# M5amigo-RS-485-MAX3485ECSA.net
KiCad netlist of a schematic drawn in EAGLE
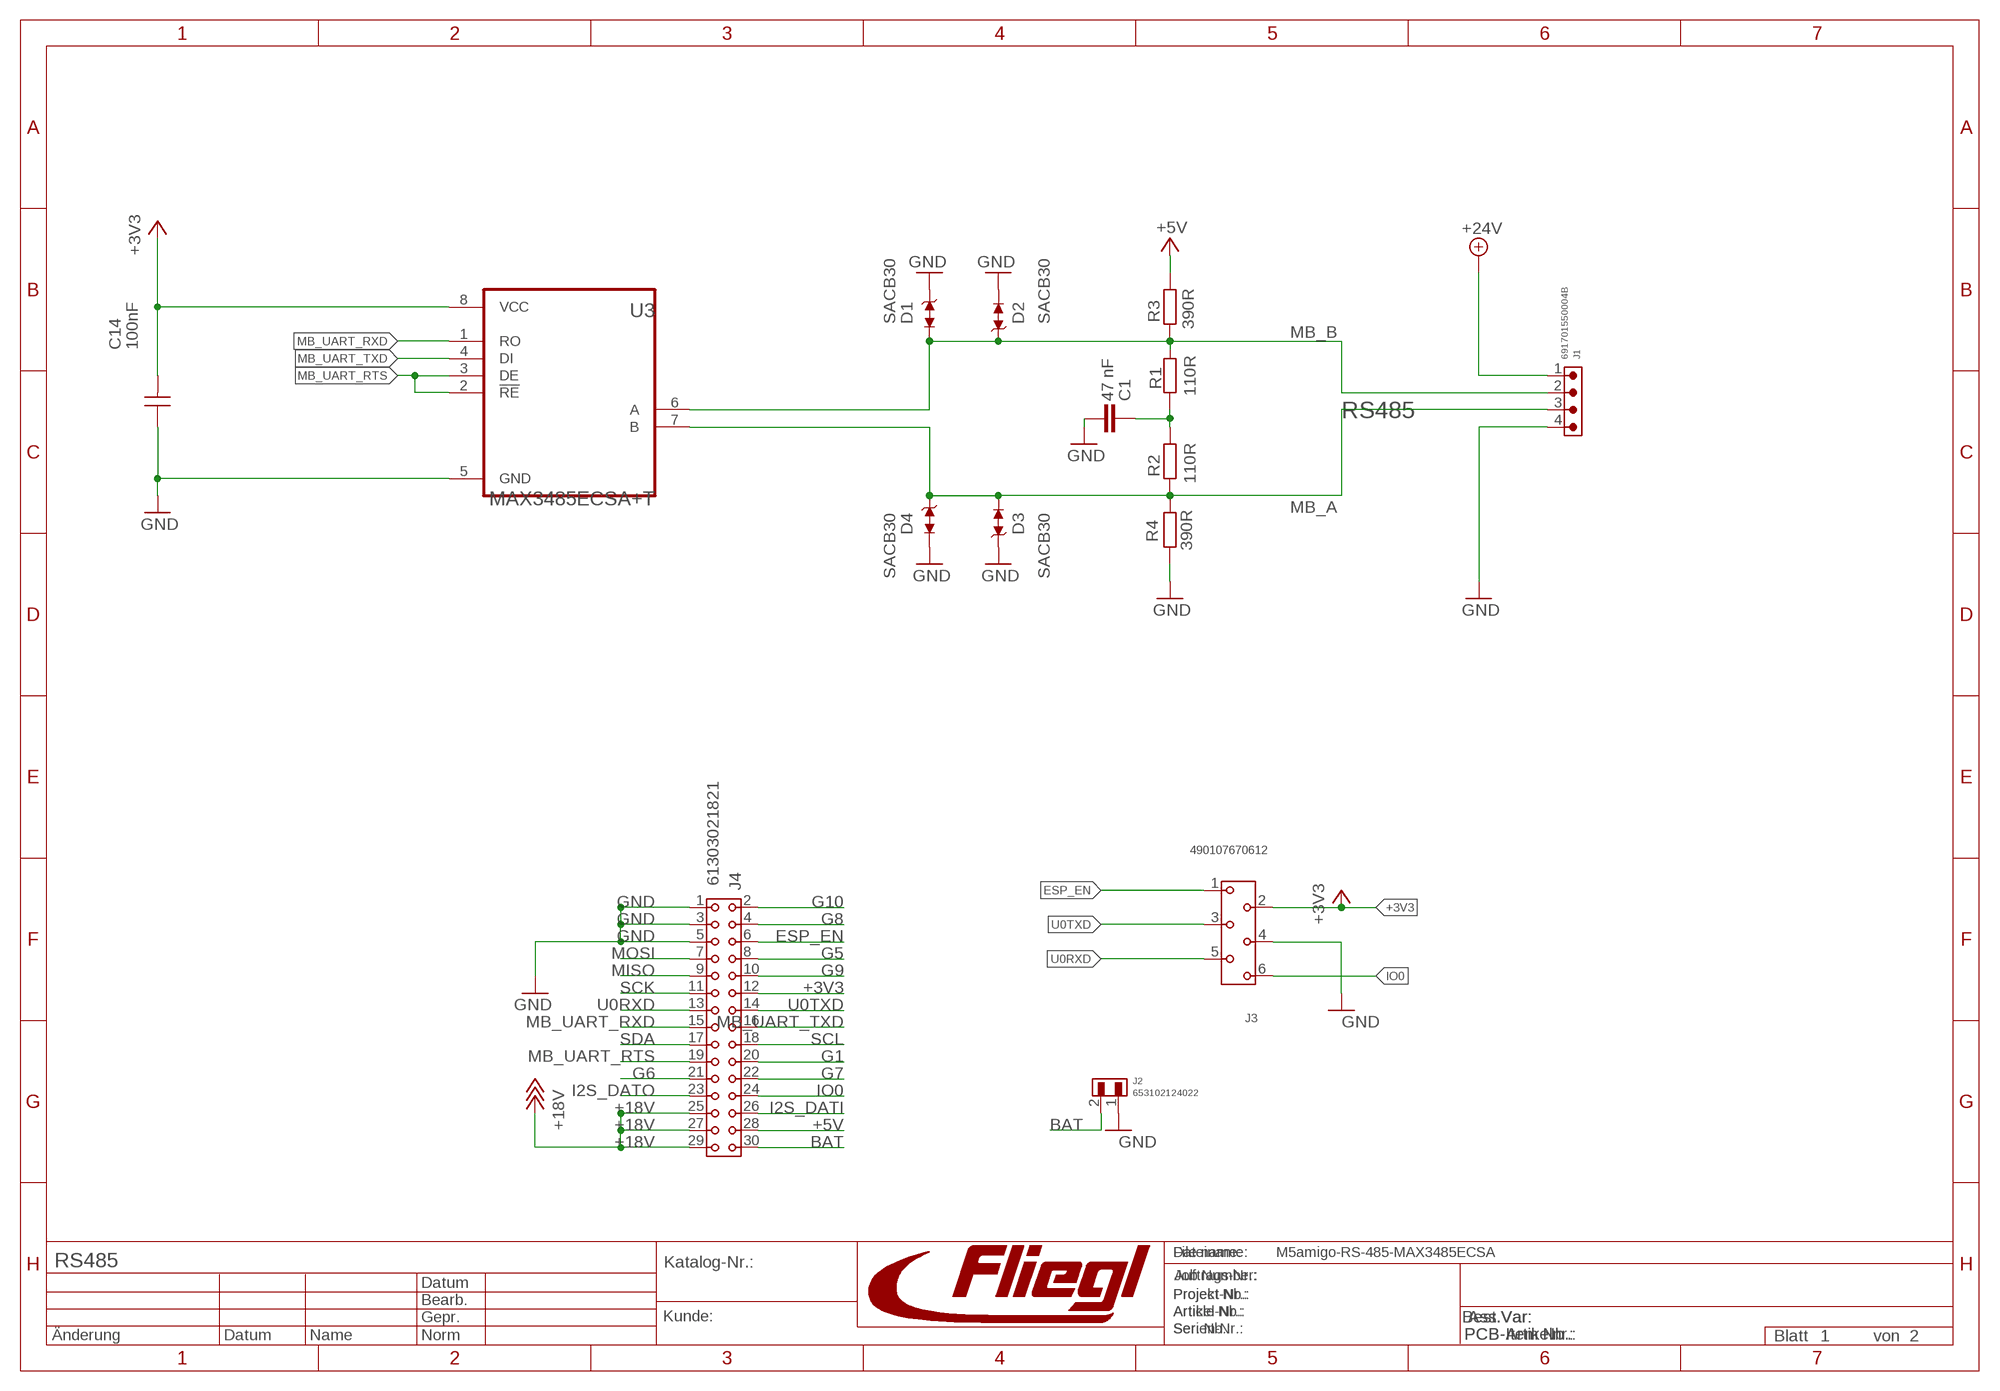
[diagram p0: schematic, sheet 1]
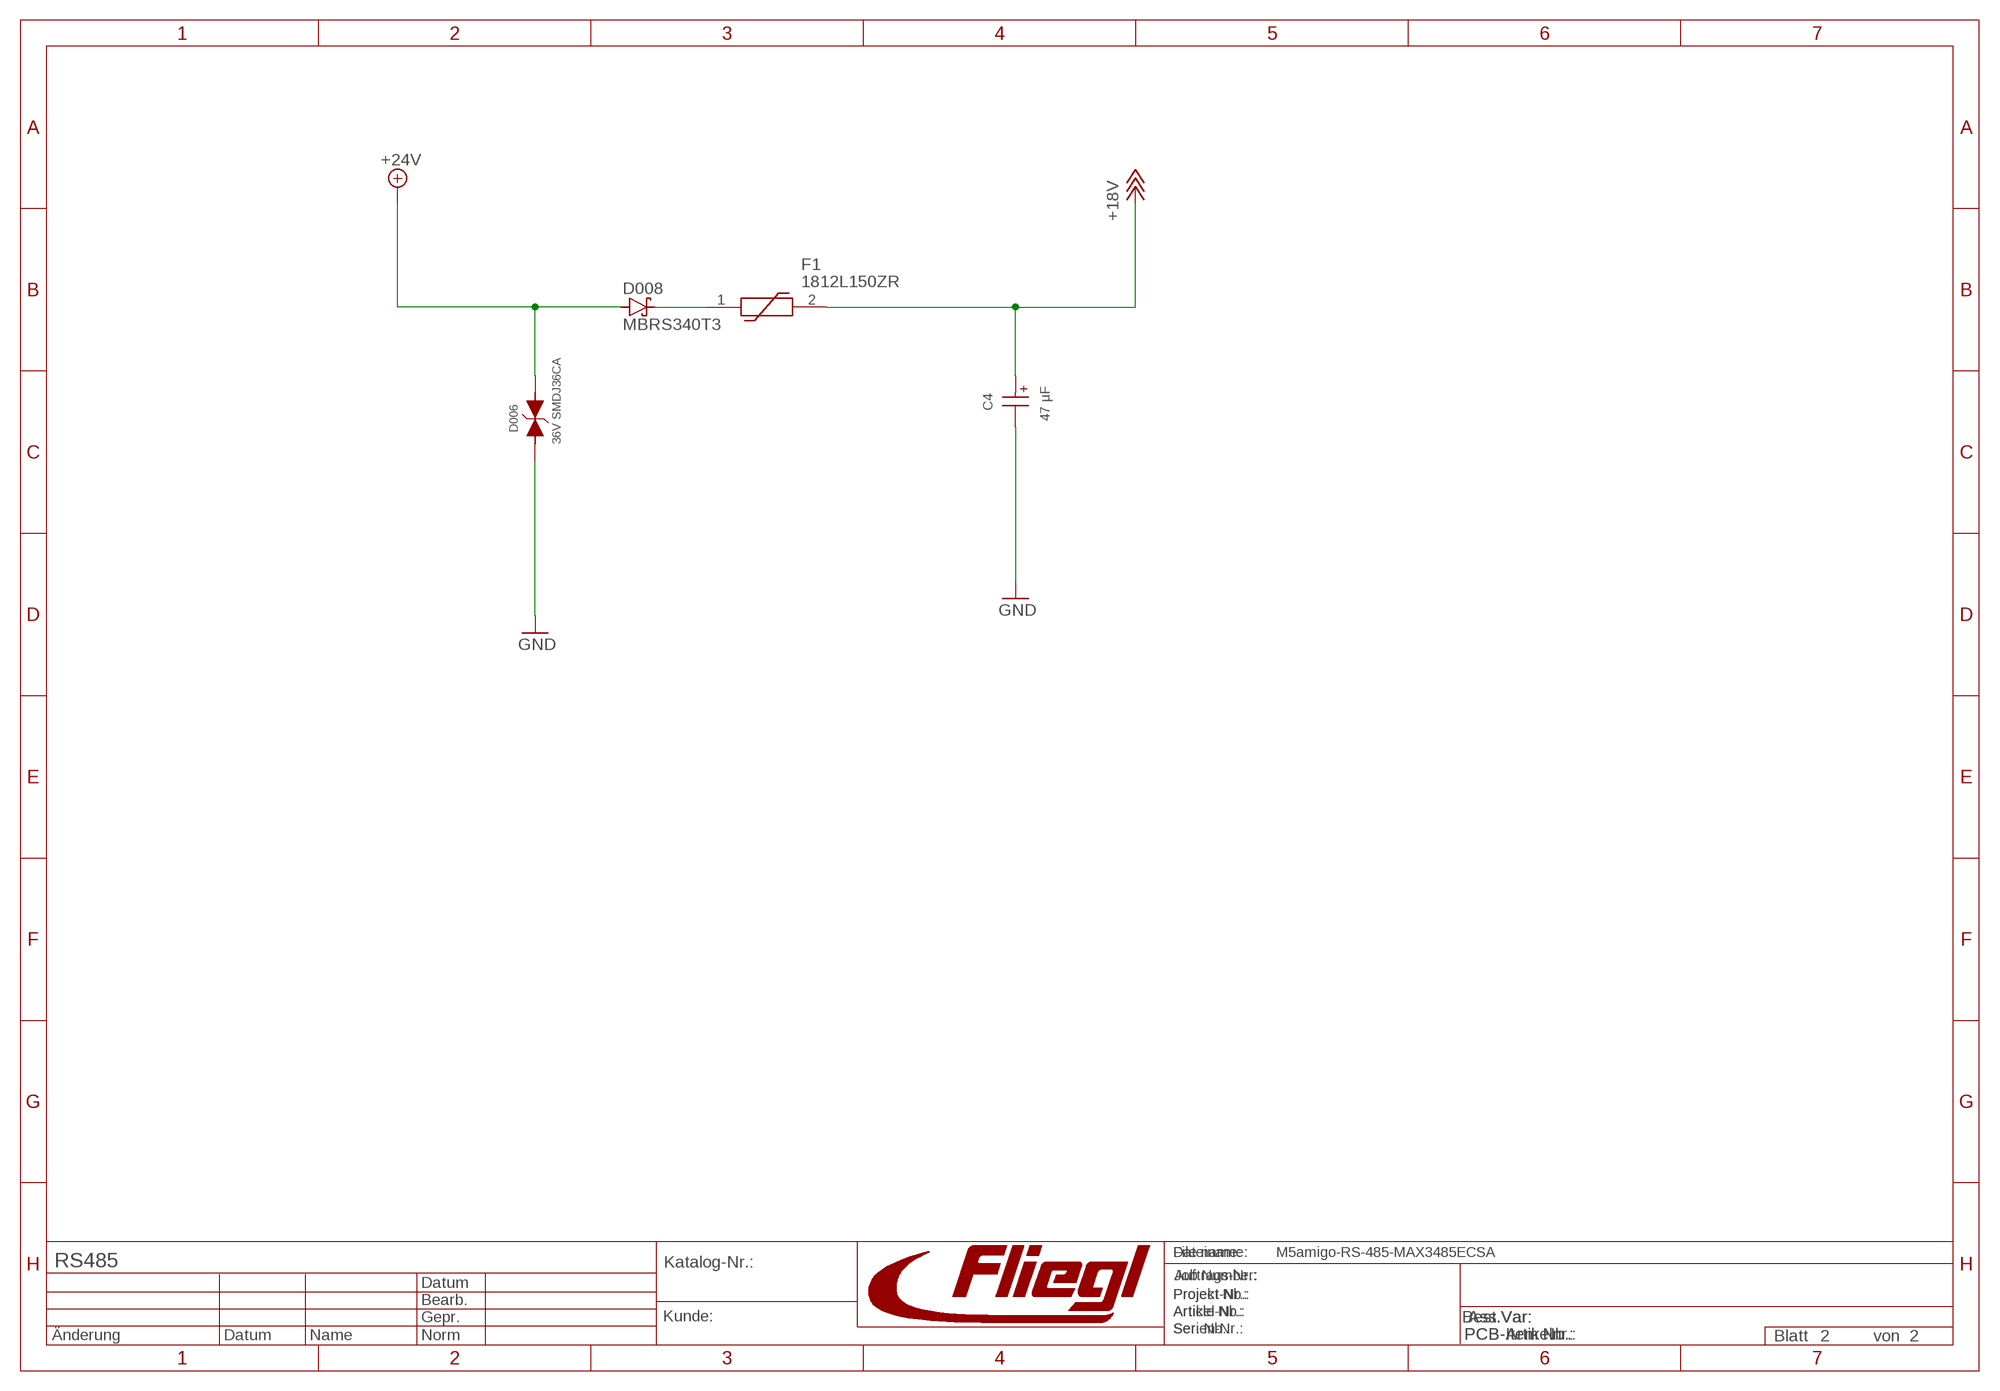
[diagram p1: schematic, sheet 2]

(export (version "E")
  (design (tool "Eeschema 10.0.6"))
  (components
    (comp (ref "C4")
      (value "47 µF")
      (footprint "eagle-import:WCAP-ASLL_6.3X7.7(DXL)")
      (libsource (lib "eagle-import") (part "WCAP-ASLL_6.3X7.7_865060645008"))
    )
    (comp (ref "D006")
      (value "36V SMDJ36CA")
      (footprint "eagle-import:WE-TVSP_DO-214AB_BIDIRECTIONAL")
      (libsource (lib "eagle-import") (part "WE-TVSP_DO-214AB_3000W_BI_824551361"))
    )
    (comp (ref "D008")
      (value "MBRS340T3")
      (footprint "eagle-import:SMC")
      (libsource (lib "eagle-import") (part "MBRS30T34"))
    )
    (comp (ref "F1")
      (value "1812L150ZR")
      (footprint "eagle-import:1812L010DR")
      (fields (field (name "MOUSER_PART_NUMBER") "576-1812L150ZR"))
      (libsource (lib "eagle-import") (part "1812L150ZR"))
    )
    (comp (ref "C1")
      (value "47 nF")
      (footprint "eagle-import:WCAP-CSGP_0402")
      (libsource (lib "eagle-import") (part "WCAP-CSGP_0402_25V(DC)_885012205054"))
    )
    (comp (ref "C14")
      (value "100nF")
      (footprint "eagle-import:WCAP-CSGP_1206_H0.8")
      (libsource (lib "eagle-import") (part "WCAP-CSGP_1206_H0.8_50V(DC)_885012208087"))
    )
    (comp (ref "D1")
      (value "SACB30")
      (footprint "eagle-import:DO214AA")
      (libsource (lib "eagle-import") (part "SACB30"))
    )
    (comp (ref "D2")
      (value "SACB30")
      (footprint "eagle-import:DO214AA")
      (libsource (lib "eagle-import") (part "SACB30"))
    )
    (comp (ref "D3")
      (value "SACB30")
      (footprint "eagle-import:DO214AA")
      (libsource (lib "eagle-import") (part "SACB30"))
    )
    (comp (ref "D4")
      (value "SACB30")
      (footprint "eagle-import:DO214AA")
      (libsource (lib "eagle-import") (part "SACB30"))
    )
    (comp (ref "J1")
      (value "691701550004B")
      (footprint "eagle-import:691701550004B")
      (libsource (lib "eagle-import") (part "691701550004B"))
    )
    (comp (ref "J2")
      (value "653102124022")
      (footprint "eagle-import:653102124022")
      (libsource (lib "eagle-import") (part "653102124022"))
    )
    (comp (ref "J3")
      (value "490107670612")
      (footprint "eagle-import:490107670612_DEBUGGING")
      (libsource (lib "eagle-import") (part "490107670612_DEBUGGING"))
    )
    (comp (ref "J4")
      (value "61303021821")
      (footprint "eagle-import:61303021821")
      (libsource (lib "eagle-import") (part "6130XX21821_61303021821"))
    )
    (comp (ref "R1")
      (value "110R")
      (footprint "eagle-import:WCAP-CSRF_0402")
      (libsource (lib "eagle-import") (part "R-0402_110R"))
    )
    (comp (ref "R2")
      (value "110R")
      (footprint "eagle-import:WCAP-CSRF_0402")
      (libsource (lib "eagle-import") (part "R-0402_110R"))
    )
    (comp (ref "R3")
      (value "390R")
      (footprint "eagle-import:WCAP-CSMH_0603_R")
      (libsource (lib "eagle-import") (part "R-0603_390R"))
    )
    (comp (ref "R4")
      (value "390R")
      (footprint "eagle-import:WCAP-CSMH_0603_R")
      (libsource (lib "eagle-import") (part "R-0603_390R"))
    )
    (comp (ref "U3")
      (value "MAX3485ECSA+T")
      (footprint "eagle-import:SOIC127P600X175-8N")
      (fields (field (name "MF") "Analog Devices"))
      (libsource (lib "eagle-import") (part "MAX3485ECSA+T"))
    )
  )
  (nets
    (net (code "1") (name "+3V3") (class "Default")
      (node (ref "C14") (pin "2") (pinfunction "2_2") (pintype "passive"))
      (node (ref "J3") (pin "2") (pinfunction "2_2") (pintype "passive"))
      (node (ref "J4") (pin "12") (pinfunction "12_12") (pintype "passive"))
      (node (ref "U3") (pin "8") (pinfunction "VCC_8") (pintype "power_in"))
    )
    (net (code "2") (name "+5V") (class "Default")
      (node (ref "J4") (pin "28") (pinfunction "28_28") (pintype "passive"))
      (node (ref "R3") (pin "2") (pinfunction "2_2") (pintype "passive"))
    )
    (net (code "3") (name "+18V") (class "Default")
      (node (ref "C4") (pin "1") (pinfunction "+_1") (pintype "passive"))
      (node (ref "F1") (pin "2") (pinfunction "2_2") (pintype "bidirectional"))
      (node (ref "J4") (pin "25") (pinfunction "25_25") (pintype "passive"))
      (node (ref "J4") (pin "27") (pinfunction "27_27") (pintype "passive"))
      (node (ref "J4") (pin "29") (pinfunction "29_29") (pintype "passive"))
    )
    (net (code "4") (name "+24V") (class "Default")
      (node (ref "D006") (pin "2") (pinfunction "2_2") (pintype "passive"))
      (node (ref "D008") (pin "A") (pinfunction "A_A") (pintype "passive"))
      (node (ref "J1") (pin "1") (pinfunction "1_1") (pintype "passive"))
    )
    (net (code "5") (name "BAT") (class "Default")
      (node (ref "J2") (pin "2") (pinfunction "2_2") (pintype "passive"))
      (node (ref "J4") (pin "30") (pinfunction "30_30") (pintype "passive"))
    )
    (net (code "6") (name "ESP_EN") (class "Default")
      (node (ref "J3") (pin "1") (pinfunction "1_1") (pintype "passive"))
      (node (ref "J4") (pin "6") (pinfunction "6_6") (pintype "passive"))
    )
    (net (code "7") (name "G1") (class "Default")
      (node (ref "J4") (pin "20") (pinfunction "20_20") (pintype "passive"))
    )
    (net (code "8") (name "G5") (class "Default")
      (node (ref "J4") (pin "8") (pinfunction "8_8") (pintype "passive"))
    )
    (net (code "9") (name "G6") (class "Default")
      (node (ref "J4") (pin "21") (pinfunction "21_21") (pintype "passive"))
    )
    (net (code "10") (name "G7") (class "Default")
      (node (ref "J4") (pin "22") (pinfunction "22_22") (pintype "passive"))
    )
    (net (code "11") (name "G8") (class "Default")
      (node (ref "J4") (pin "4") (pinfunction "4_4") (pintype "passive"))
    )
    (net (code "12") (name "G9") (class "Default")
      (node (ref "J4") (pin "10") (pinfunction "10_10") (pintype "passive"))
    )
    (net (code "13") (name "G10") (class "Default")
      (node (ref "J4") (pin "2") (pinfunction "2_2") (pintype "passive"))
    )
    (net (code "14") (name "GND") (class "Default")
      (node (ref "C1") (pin "2") (pinfunction "2_2") (pintype "passive"))
      (node (ref "C14") (pin "1") (pinfunction "1_1") (pintype "passive"))
      (node (ref "C4") (pin "2") (pinfunction "-_2") (pintype "passive"))
      (node (ref "D006") (pin "1") (pinfunction "1_1") (pintype "passive"))
      (node (ref "D1") (pin "C") (pinfunction "K_C") (pintype "passive"))
      (node (ref "D2") (pin "A") (pinfunction "KD_A") (pintype "passive"))
      (node (ref "D3") (pin "C") (pinfunction "K_C") (pintype "passive"))
      (node (ref "D4") (pin "A") (pinfunction "KD_A") (pintype "passive"))
      (node (ref "J1") (pin "4") (pinfunction "4_4") (pintype "passive"))
      (node (ref "J2") (pin "1") (pinfunction "1_1") (pintype "passive"))
      (node (ref "J3") (pin "4") (pinfunction "4_4") (pintype "passive"))
      (node (ref "J4") (pin "1") (pinfunction "1_1") (pintype "passive"))
      (node (ref "J4") (pin "3") (pinfunction "3_3") (pintype "passive"))
      (node (ref "J4") (pin "5") (pinfunction "5_5") (pintype "passive"))
      (node (ref "R4") (pin "1") (pinfunction "1_1") (pintype "passive"))
      (node (ref "U3") (pin "5") (pinfunction "GND_5") (pintype "power_in"))
    )
    (net (code "15") (name "I2S_DATI") (class "Default")
      (node (ref "J4") (pin "26") (pinfunction "26_26") (pintype "passive"))
    )
    (net (code "16") (name "I2S_DATO") (class "Default")
      (node (ref "J4") (pin "23") (pinfunction "23_23") (pintype "passive"))
    )
    (net (code "17") (name "IO0") (class "Default")
      (node (ref "J3") (pin "6") (pinfunction "6_6") (pintype "passive"))
      (node (ref "J4") (pin "24") (pinfunction "24_24") (pintype "passive"))
    )
    (net (code "18") (name "MB_A") (class "Default")
      (node (ref "D3") (pin "A") (pinfunction "KD_A") (pintype "passive"))
      (node (ref "D4") (pin "C") (pinfunction "K_C") (pintype "passive"))
      (node (ref "J1") (pin "3") (pinfunction "3_3") (pintype "passive"))
      (node (ref "R2") (pin "1") (pinfunction "1_1") (pintype "passive"))
      (node (ref "R4") (pin "2") (pinfunction "2_2") (pintype "passive"))
      (node (ref "U3") (pin "7") (pinfunction "B_7") (pintype "bidirectional"))
    )
    (net (code "19") (name "MB_B") (class "Default")
      (node (ref "D1") (pin "A") (pinfunction "KD_A") (pintype "passive"))
      (node (ref "D2") (pin "C") (pinfunction "K_C") (pintype "passive"))
      (node (ref "J1") (pin "2") (pinfunction "2_2") (pintype "passive"))
      (node (ref "R1") (pin "2") (pinfunction "2_2") (pintype "passive"))
      (node (ref "R3") (pin "1") (pinfunction "1_1") (pintype "passive"))
      (node (ref "U3") (pin "6") (pinfunction "A_6") (pintype "bidirectional"))
    )
    (net (code "20") (name "MB_UART_RTS") (class "Default")
      (node (ref "J4") (pin "19") (pinfunction "19_19") (pintype "passive"))
      (node (ref "U3") (pin "2") (pinfunction "~{RE}_2") (pintype "input"))
      (node (ref "U3") (pin "3") (pinfunction "DE_3") (pintype "input"))
    )
    (net (code "21") (name "MB_UART_RXD") (class "Default")
      (node (ref "J4") (pin "15") (pinfunction "15_15") (pintype "passive"))
      (node (ref "U3") (pin "1") (pinfunction "RO_1") (pintype "output"))
    )
    (net (code "22") (name "MB_UART_TXD") (class "Default")
      (node (ref "J4") (pin "16") (pinfunction "16_16") (pintype "passive"))
      (node (ref "U3") (pin "4") (pinfunction "DI_4") (pintype "input"))
    )
    (net (code "23") (name "MISO") (class "Default")
      (node (ref "J4") (pin "9") (pinfunction "9_9") (pintype "passive"))
    )
    (net (code "24") (name "MOSI") (class "Default")
      (node (ref "J4") (pin "7") (pinfunction "7_7") (pintype "passive"))
    )
    (net (code "25") (name "Net-(C1-Pad1)") (class "Default")
      (node (ref "C1") (pin "1") (pinfunction "1_1") (pintype "passive"))
      (node (ref "R1") (pin "1") (pinfunction "1_1") (pintype "passive"))
      (node (ref "R2") (pin "2") (pinfunction "2_2") (pintype "passive"))
    )
    (net (code "26") (name "Net-(D008-PadC)") (class "Default")
      (node (ref "D008") (pin "C") (pinfunction "C_C") (pintype "passive"))
      (node (ref "F1") (pin "1") (pinfunction "1_1") (pintype "bidirectional"))
    )
    (net (code "27") (name "SCK") (class "Default")
      (node (ref "J4") (pin "11") (pinfunction "11_11") (pintype "passive"))
    )
    (net (code "28") (name "SCL") (class "Default")
      (node (ref "J4") (pin "18") (pinfunction "18_18") (pintype "passive"))
    )
    (net (code "29") (name "SDA") (class "Default")
      (node (ref "J4") (pin "17") (pinfunction "17_17") (pintype "passive"))
    )
    (net (code "30") (name "U0RXD") (class "Default")
      (node (ref "J3") (pin "5") (pinfunction "5_5") (pintype "passive"))
      (node (ref "J4") (pin "13") (pinfunction "13_13") (pintype "passive"))
    )
    (net (code "31") (name "U0TXD") (class "Default")
      (node (ref "J3") (pin "3") (pinfunction "3_3") (pintype "passive"))
      (node (ref "J4") (pin "14") (pinfunction "14_14") (pintype "passive"))
    )
  )
)
